# untitled.net
KiCad netlist of a schematic drawn in EAGLE
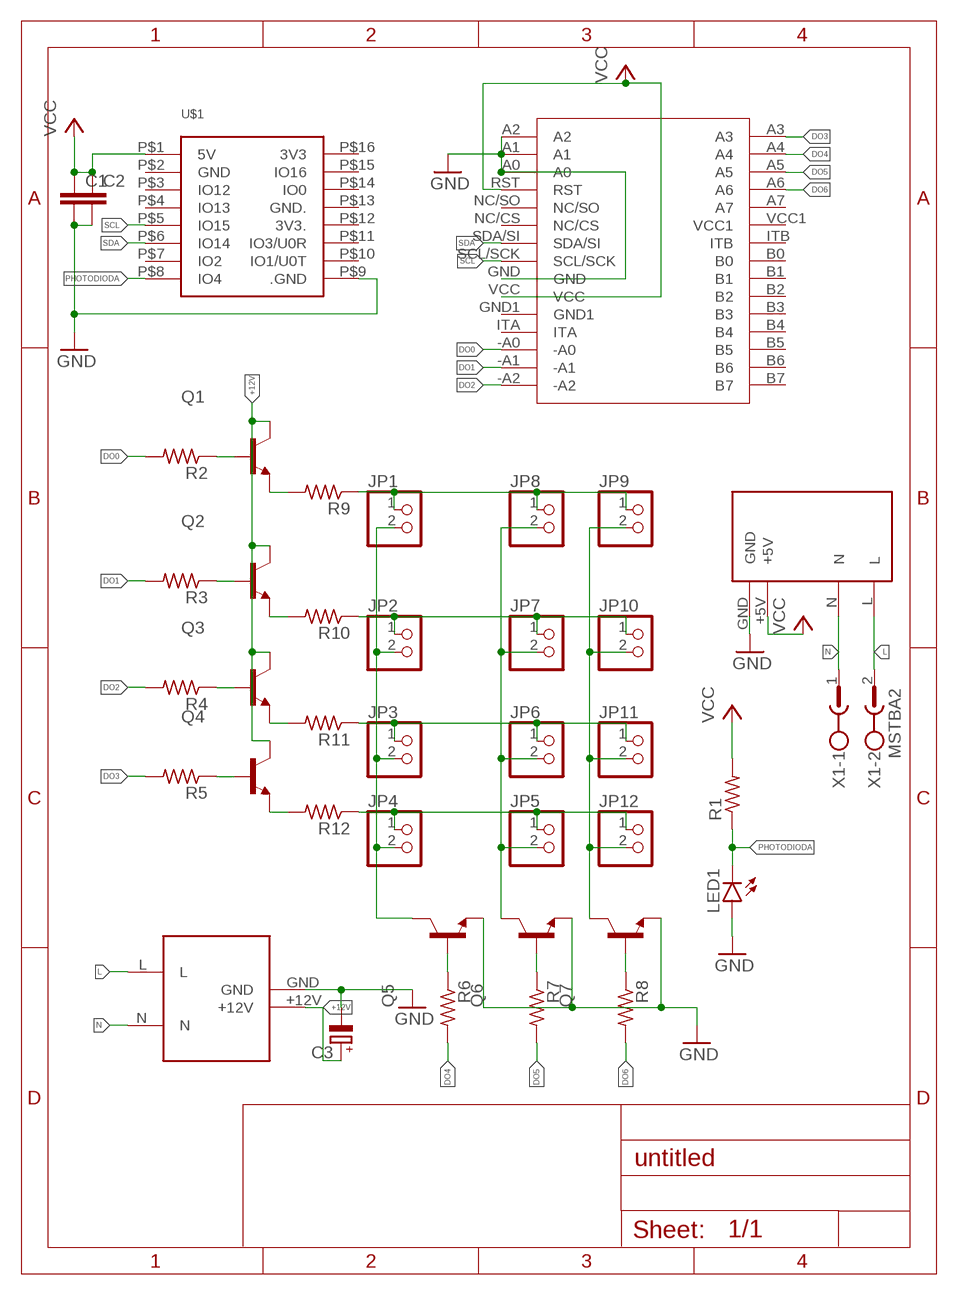
[diagram p0: schematic, sheet 1]

(export (version "E")
  (design (tool "Eeschema 10.0.6"))
  (components
    (comp (ref "C1")
      (value "C-EUC0805K")
      (footprint "eagle-import:C0805K")
      (libsource (lib "eagle-import") (part "C-EUC0805K"))
    )
    (comp (ref "C2")
      (value "C-EUC0805K")
      (footprint "eagle-import:C0805K")
      (libsource (lib "eagle-import") (part "C-EUC0805K"))
    )
    (comp (ref "C3")
      (value "CPOL-EU153CLV-0505")
      (footprint "eagle-import:153CLV-0505")
      (libsource (lib "eagle-import") (part "CPOL-EU153CLV-0505"))
    )
    (comp (ref "HLK-15M1")
      (value "HLK-15M12")
      (footprint "eagle-import:HLK-15M12")
      (libsource (lib "eagle-import") (part "HLK-15M12"))
    )
    (comp (ref "JP1")
      (value "PINHD-1X2")
      (footprint "eagle-import:1X02")
      (libsource (lib "eagle-import") (part "PINHD-1X2"))
    )
    (comp (ref "JP2")
      (value "PINHD-1X2")
      (footprint "eagle-import:1X02")
      (libsource (lib "eagle-import") (part "PINHD-1X2"))
    )
    (comp (ref "JP3")
      (value "PINHD-1X2")
      (footprint "eagle-import:1X02")
      (libsource (lib "eagle-import") (part "PINHD-1X2"))
    )
    (comp (ref "JP4")
      (value "PINHD-1X2")
      (footprint "eagle-import:1X02")
      (libsource (lib "eagle-import") (part "PINHD-1X2"))
    )
    (comp (ref "JP5")
      (value "PINHD-1X2")
      (footprint "eagle-import:1X02")
      (libsource (lib "eagle-import") (part "PINHD-1X2"))
    )
    (comp (ref "JP6")
      (value "PINHD-1X2")
      (footprint "eagle-import:1X02")
      (libsource (lib "eagle-import") (part "PINHD-1X2"))
    )
    (comp (ref "JP7")
      (value "PINHD-1X2")
      (footprint "eagle-import:1X02")
      (libsource (lib "eagle-import") (part "PINHD-1X2"))
    )
    (comp (ref "JP8")
      (value "PINHD-1X2")
      (footprint "eagle-import:1X02")
      (libsource (lib "eagle-import") (part "PINHD-1X2"))
    )
    (comp (ref "JP9")
      (value "PINHD-1X2")
      (footprint "eagle-import:1X02")
      (libsource (lib "eagle-import") (part "PINHD-1X2"))
    )
    (comp (ref "JP10")
      (value "PINHD-1X2")
      (footprint "eagle-import:1X02")
      (libsource (lib "eagle-import") (part "PINHD-1X2"))
    )
    (comp (ref "JP11")
      (value "PINHD-1X2")
      (footprint "eagle-import:1X02")
      (libsource (lib "eagle-import") (part "PINHD-1X2"))
    )
    (comp (ref "JP12")
      (value "PINHD-1X2")
      (footprint "eagle-import:1X02")
      (libsource (lib "eagle-import") (part "PINHD-1X2"))
    )
    (comp (ref "LED1")
      (value "LED5MM")
      (footprint "eagle-import:LED5MM")
      (libsource (lib "eagle-import") (part "LED5MM"))
    )
    (comp (ref "MCP1")
      (value "MCP23017")
      (footprint "eagle-import:MCP23017")
      (libsource (lib "eagle-import") (part "MCP23017"))
    )
    (comp (ref "Q1")
      (value "BCW31SMD")
      (footprint "eagle-import:SOT23-BEC")
      (fields (field (name "MF") "ON Semiconductor") (field (name "MP") "BCW31"))
      (libsource (lib "eagle-import") (part "BCW31SMD"))
    )
    (comp (ref "Q2")
      (value "BCW31SMD")
      (footprint "eagle-import:SOT23-BEC")
      (fields (field (name "MF") "ON Semiconductor") (field (name "MP") "BCW31"))
      (libsource (lib "eagle-import") (part "BCW31SMD"))
    )
    (comp (ref "Q3")
      (value "BCW31SMD")
      (footprint "eagle-import:SOT23-BEC")
      (fields (field (name "MF") "ON Semiconductor") (field (name "MP") "BCW31"))
      (libsource (lib "eagle-import") (part "BCW31SMD"))
    )
    (comp (ref "Q4")
      (value "BCW31SMD")
      (footprint "eagle-import:SOT23-BEC")
      (fields (field (name "MF") "ON Semiconductor") (field (name "MP") "BCW31"))
      (libsource (lib "eagle-import") (part "BCW31SMD"))
    )
    (comp (ref "Q5")
      (value "BCW31SMD")
      (footprint "eagle-import:SOT23-BEC")
      (fields (field (name "MF") "ON Semiconductor") (field (name "MP") "BCW31"))
      (libsource (lib "eagle-import") (part "BCW31SMD"))
    )
    (comp (ref "Q6")
      (value "BCW31SMD")
      (footprint "eagle-import:SOT23-BEC")
      (fields (field (name "MF") "ON Semiconductor") (field (name "MP") "BCW31"))
      (libsource (lib "eagle-import") (part "BCW31SMD"))
    )
    (comp (ref "Q7")
      (value "BCW31SMD")
      (footprint "eagle-import:SOT23-BEC")
      (fields (field (name "MF") "ON Semiconductor") (field (name "MP") "BCW31"))
      (libsource (lib "eagle-import") (part "BCW31SMD"))
    )
    (comp (ref "R1")
      (value "R-US_M0805")
      (footprint "eagle-import:M0805")
      (libsource (lib "eagle-import") (part "R-US_M0805"))
    )
    (comp (ref "R2")
      (value "R-US_M0805")
      (footprint "eagle-import:M0805")
      (libsource (lib "eagle-import") (part "R-US_M0805"))
    )
    (comp (ref "R3")
      (value "R-US_M0805")
      (footprint "eagle-import:M0805")
      (libsource (lib "eagle-import") (part "R-US_M0805"))
    )
    (comp (ref "R4")
      (value "R-US_M0805")
      (footprint "eagle-import:M0805")
      (libsource (lib "eagle-import") (part "R-US_M0805"))
    )
    (comp (ref "R5")
      (value "R-US_M0805")
      (footprint "eagle-import:M0805")
      (libsource (lib "eagle-import") (part "R-US_M0805"))
    )
    (comp (ref "R6")
      (value "R-US_M0805")
      (footprint "eagle-import:M0805")
      (libsource (lib "eagle-import") (part "R-US_M0805"))
    )
    (comp (ref "R7")
      (value "R-US_M0805")
      (footprint "eagle-import:M0805")
      (libsource (lib "eagle-import") (part "R-US_M0805"))
    )
    (comp (ref "R8")
      (value "R-US_M0805")
      (footprint "eagle-import:M0805")
      (libsource (lib "eagle-import") (part "R-US_M0805"))
    )
    (comp (ref "R9")
      (value "R-US_M0805")
      (footprint "eagle-import:M0805")
      (libsource (lib "eagle-import") (part "R-US_M0805"))
    )
    (comp (ref "R10")
      (value "R-US_M0805")
      (footprint "eagle-import:M0805")
      (libsource (lib "eagle-import") (part "R-US_M0805"))
    )
    (comp (ref "R11")
      (value "R-US_M0805")
      (footprint "eagle-import:M0805")
      (libsource (lib "eagle-import") (part "R-US_M0805"))
    )
    (comp (ref "R12")
      (value "R-US_M0805")
      (footprint "eagle-import:M0805")
      (libsource (lib "eagle-import") (part "R-US_M0805"))
    )
    (comp (ref "U$1")
      (value "ESP32-CAM")
      (footprint "eagle-import:ESP32-CAM")
      (fields (field (name "MF") "AI-Thinker"))
      (libsource (lib "eagle-import") (part "ESP32-CAM"))
    )
    (comp (ref "WX-DC1")
      (value "WX-DC12003")
      (footprint "eagle-import:WX-DC12003")
      (libsource (lib "eagle-import") (part "WX-DC12003"))
    )
    (comp (ref "X1")
      (value "MSTBA2")
      (footprint "eagle-import:MSTBA2")
      (fields (field (name "MF") "FARNELL") (field (name "MPN") "1757242"))
      (libsource (lib "eagle-import") (part "MSTBA2"))
    )
  )
  (nets
    (net (code "1") (name "+12V") (class "Default")
      (node (ref "C3") (pin "+") (pinfunction "+_+") (pintype "passive"))
      (node (ref "HLK-15M1") (pin "+12V") (pinfunction "+12V_+12V") (pintype "bidirectional"))
      (node (ref "Q1") (pin "C") (pinfunction "C_C") (pintype "passive"))
      (node (ref "Q2") (pin "C") (pinfunction "C_C") (pintype "passive"))
      (node (ref "Q3") (pin "C") (pinfunction "C_C") (pintype "passive"))
      (node (ref "Q4") (pin "C") (pinfunction "C_C") (pintype "passive"))
    )
    (net (code "2") (name "DO0") (class "Default")
      (node (ref "MCP1") (pin "-A0") (pinfunction "-A0_-A0") (pintype "bidirectional"))
      (node (ref "R2") (pin "2") (pinfunction "2_2") (pintype "passive"))
    )
    (net (code "3") (name "DO1") (class "Default")
      (node (ref "MCP1") (pin "-A1") (pinfunction "-A1_-A1") (pintype "bidirectional"))
      (node (ref "R3") (pin "2") (pinfunction "2_2") (pintype "passive"))
    )
    (net (code "4") (name "DO2") (class "Default")
      (node (ref "MCP1") (pin "-A2") (pinfunction "-A2_-A2") (pintype "bidirectional"))
      (node (ref "R4") (pin "2") (pinfunction "2_2") (pintype "passive"))
    )
    (net (code "5") (name "DO3") (class "Default")
      (node (ref "MCP1") (pin "A3") (pinfunction "A3_A3") (pintype "bidirectional"))
      (node (ref "R5") (pin "2") (pinfunction "2_2") (pintype "passive"))
    )
    (net (code "6") (name "DO4") (class "Default")
      (node (ref "MCP1") (pin "A4") (pinfunction "A4_A4") (pintype "bidirectional"))
      (node (ref "R6") (pin "2") (pinfunction "2_2") (pintype "passive"))
    )
    (net (code "7") (name "DO5") (class "Default")
      (node (ref "MCP1") (pin "A5") (pinfunction "A5_A5") (pintype "bidirectional"))
      (node (ref "R7") (pin "2") (pinfunction "2_2") (pintype "passive"))
    )
    (net (code "8") (name "DO6") (class "Default")
      (node (ref "MCP1") (pin "A6") (pinfunction "A6_A6") (pintype "bidirectional"))
      (node (ref "R8") (pin "2") (pinfunction "2_2") (pintype "passive"))
    )
    (net (code "9") (name "GND") (class "Default")
      (node (ref "C1") (pin "2") (pinfunction "2_2") (pintype "passive"))
      (node (ref "C2") (pin "2") (pinfunction "2_2") (pintype "passive"))
      (node (ref "C3") (pin "-") (pinfunction "-_-") (pintype "passive"))
      (node (ref "HLK-15M1") (pin "GND") (pinfunction "GND_GND") (pintype "bidirectional"))
      (node (ref "LED1") (pin "A") (pinfunction "A_A") (pintype "passive"))
      (node (ref "MCP1") (pin "A0") (pinfunction "A0_A0") (pintype "bidirectional"))
      (node (ref "MCP1") (pin "A1") (pinfunction "A1_A1") (pintype "bidirectional"))
      (node (ref "MCP1") (pin "A2") (pinfunction "A2_A2") (pintype "bidirectional"))
      (node (ref "MCP1") (pin "GND") (pinfunction "GND_GND") (pintype "bidirectional"))
      (node (ref "Q5") (pin "E") (pinfunction "E_E") (pintype "passive"))
      (node (ref "Q6") (pin "E") (pinfunction "E_E") (pintype "passive"))
      (node (ref "Q7") (pin "E") (pinfunction "E_E") (pintype "passive"))
      (node (ref "U$1") (pin "P$9") (pinfunction ".GND_P$9") (pintype "bidirectional"))
      (node (ref "WX-DC1") (pin "GND") (pinfunction "GND_GND") (pintype "bidirectional"))
    )
    (net (code "10") (name "L") (class "Default")
      (node (ref "HLK-15M1") (pin "L") (pinfunction "L_L") (pintype "bidirectional"))
      (node (ref "WX-DC1") (pin "L") (pinfunction "L_L") (pintype "bidirectional"))
      (node (ref "X1") (pin "2") (pinfunction "1_2") (pintype "passive"))
    )
    (net (code "11") (name "N") (class "Default")
      (node (ref "HLK-15M1") (pin "N") (pinfunction "N_N") (pintype "bidirectional"))
      (node (ref "WX-DC1") (pin "N") (pinfunction "N_N") (pintype "bidirectional"))
      (node (ref "X1") (pin "1") (pinfunction "1_1") (pintype "passive"))
    )
    (net (code "12") (name "Net-(JP1-Pad1)") (class "Default")
      (node (ref "JP1") (pin "1") (pinfunction "1_1") (pintype "passive"))
      (node (ref "JP8") (pin "1") (pinfunction "1_1") (pintype "passive"))
      (node (ref "JP9") (pin "1") (pinfunction "1_1") (pintype "passive"))
      (node (ref "R9") (pin "1") (pinfunction "1_1") (pintype "passive"))
    )
    (net (code "13") (name "Net-(JP1-Pad2)") (class "Default")
      (node (ref "JP1") (pin "2") (pinfunction "2_2") (pintype "passive"))
      (node (ref "JP2") (pin "2") (pinfunction "2_2") (pintype "passive"))
      (node (ref "JP3") (pin "2") (pinfunction "2_2") (pintype "passive"))
      (node (ref "JP4") (pin "2") (pinfunction "2_2") (pintype "passive"))
      (node (ref "Q5") (pin "C") (pinfunction "C_C") (pintype "passive"))
    )
    (net (code "14") (name "Net-(JP5-Pad2)") (class "Default")
      (node (ref "JP5") (pin "2") (pinfunction "2_2") (pintype "passive"))
      (node (ref "JP6") (pin "2") (pinfunction "2_2") (pintype "passive"))
      (node (ref "JP7") (pin "2") (pinfunction "2_2") (pintype "passive"))
      (node (ref "JP8") (pin "2") (pinfunction "2_2") (pintype "passive"))
      (node (ref "Q6") (pin "C") (pinfunction "C_C") (pintype "passive"))
    )
    (net (code "15") (name "Net-(JP10-Pad1)") (class "Default")
      (node (ref "JP10") (pin "1") (pinfunction "1_1") (pintype "passive"))
      (node (ref "JP2") (pin "1") (pinfunction "1_1") (pintype "passive"))
      (node (ref "JP7") (pin "1") (pinfunction "1_1") (pintype "passive"))
      (node (ref "R10") (pin "1") (pinfunction "1_1") (pintype "passive"))
    )
    (net (code "16") (name "Net-(JP10-Pad2)") (class "Default")
      (node (ref "JP10") (pin "2") (pinfunction "2_2") (pintype "passive"))
      (node (ref "JP11") (pin "2") (pinfunction "2_2") (pintype "passive"))
      (node (ref "JP12") (pin "2") (pinfunction "2_2") (pintype "passive"))
      (node (ref "JP9") (pin "2") (pinfunction "2_2") (pintype "passive"))
      (node (ref "Q7") (pin "C") (pinfunction "C_C") (pintype "passive"))
    )
    (net (code "17") (name "Net-(JP11-Pad1)") (class "Default")
      (node (ref "JP11") (pin "1") (pinfunction "1_1") (pintype "passive"))
      (node (ref "JP3") (pin "1") (pinfunction "1_1") (pintype "passive"))
      (node (ref "JP6") (pin "1") (pinfunction "1_1") (pintype "passive"))
      (node (ref "R11") (pin "1") (pinfunction "1_1") (pintype "passive"))
    )
    (net (code "18") (name "Net-(JP12-Pad1)") (class "Default")
      (node (ref "JP12") (pin "1") (pinfunction "1_1") (pintype "passive"))
      (node (ref "JP4") (pin "1") (pinfunction "1_1") (pintype "passive"))
      (node (ref "JP5") (pin "1") (pinfunction "1_1") (pintype "passive"))
      (node (ref "R12") (pin "1") (pinfunction "1_1") (pintype "passive"))
    )
    (net (code "19") (name "Net-(Q1-PadB)") (class "Default")
      (node (ref "Q1") (pin "B") (pinfunction "B_B") (pintype "passive"))
      (node (ref "R2") (pin "1") (pinfunction "1_1") (pintype "passive"))
    )
    (net (code "20") (name "Net-(Q1-PadE)") (class "Default")
      (node (ref "Q1") (pin "E") (pinfunction "E_E") (pintype "passive"))
      (node (ref "R9") (pin "2") (pinfunction "2_2") (pintype "passive"))
    )
    (net (code "21") (name "Net-(Q2-PadB)") (class "Default")
      (node (ref "Q2") (pin "B") (pinfunction "B_B") (pintype "passive"))
      (node (ref "R3") (pin "1") (pinfunction "1_1") (pintype "passive"))
    )
    (net (code "22") (name "Net-(Q2-PadE)") (class "Default")
      (node (ref "Q2") (pin "E") (pinfunction "E_E") (pintype "passive"))
      (node (ref "R10") (pin "2") (pinfunction "2_2") (pintype "passive"))
    )
    (net (code "23") (name "Net-(Q3-PadB)") (class "Default")
      (node (ref "Q3") (pin "B") (pinfunction "B_B") (pintype "passive"))
      (node (ref "R4") (pin "1") (pinfunction "1_1") (pintype "passive"))
    )
    (net (code "24") (name "Net-(Q3-PadE)") (class "Default")
      (node (ref "Q3") (pin "E") (pinfunction "E_E") (pintype "passive"))
      (node (ref "R11") (pin "2") (pinfunction "2_2") (pintype "passive"))
    )
    (net (code "25") (name "Net-(Q4-PadB)") (class "Default")
      (node (ref "Q4") (pin "B") (pinfunction "B_B") (pintype "passive"))
      (node (ref "R5") (pin "1") (pinfunction "1_1") (pintype "passive"))
    )
    (net (code "26") (name "Net-(Q4-PadE)") (class "Default")
      (node (ref "Q4") (pin "E") (pinfunction "E_E") (pintype "passive"))
      (node (ref "R12") (pin "2") (pinfunction "2_2") (pintype "passive"))
    )
    (net (code "27") (name "Net-(Q5-PadB)") (class "Default")
      (node (ref "Q5") (pin "B") (pinfunction "B_B") (pintype "passive"))
      (node (ref "R6") (pin "1") (pinfunction "1_1") (pintype "passive"))
    )
    (net (code "28") (name "Net-(Q6-PadB)") (class "Default")
      (node (ref "Q6") (pin "B") (pinfunction "B_B") (pintype "passive"))
      (node (ref "R7") (pin "1") (pinfunction "1_1") (pintype "passive"))
    )
    (net (code "29") (name "Net-(Q7-PadB)") (class "Default")
      (node (ref "Q7") (pin "B") (pinfunction "B_B") (pintype "passive"))
      (node (ref "R8") (pin "1") (pinfunction "1_1") (pintype "passive"))
    )
    (net (code "30") (name "PHOTODIODA") (class "Default")
      (node (ref "LED1") (pin "K") (pinfunction "C_K") (pintype "passive"))
      (node (ref "R1") (pin "1") (pinfunction "1_1") (pintype "passive"))
      (node (ref "U$1") (pin "P$8") (pinfunction "IO4_P$8") (pintype "bidirectional"))
    )
    (net (code "31") (name "SCL") (class "Default")
      (node (ref "MCP1") (pin "SCL/SCK") (pinfunction "SCL/SCK_SCL/SCK") (pintype "bidirectional"))
      (node (ref "U$1") (pin "P$5") (pinfunction "IO15_P$5") (pintype "bidirectional"))
    )
    (net (code "32") (name "SDA") (class "Default")
      (node (ref "MCP1") (pin "SDA/SI") (pinfunction "SDA/SI_SDA/SI") (pintype "bidirectional"))
      (node (ref "U$1") (pin "P$6") (pinfunction "IO14_P$6") (pintype "bidirectional"))
    )
    (net (code "33") (name "VCC") (class "Default")
      (node (ref "C1") (pin "1") (pinfunction "1_1") (pintype "passive"))
      (node (ref "C2") (pin "1") (pinfunction "1_1") (pintype "passive"))
      (node (ref "MCP1") (pin "RST") (pinfunction "RST_RST") (pintype "bidirectional"))
      (node (ref "MCP1") (pin "VCC") (pinfunction "VCC_VCC") (pintype "bidirectional"))
      (node (ref "R1") (pin "2") (pinfunction "2_2") (pintype "passive"))
      (node (ref "U$1") (pin "P$1") (pinfunction "5V_P$1") (pintype "bidirectional"))
      (node (ref "WX-DC1") (pin "+5V") (pinfunction "+5V_+5V") (pintype "bidirectional"))
    )
    (net (code "34") (name "unconnected-(MCP1-PadA7)") (class "Default")
      (node (ref "MCP1") (pin "A7") (pinfunction "A7_A7") (pintype "bidirectional"))
    )
    (net (code "35") (name "unconnected-(MCP1-PadB0)") (class "Default")
      (node (ref "MCP1") (pin "B0") (pinfunction "B0_B0") (pintype "bidirectional"))
    )
    (net (code "36") (name "unconnected-(MCP1-PadB1)") (class "Default")
      (node (ref "MCP1") (pin "B1") (pinfunction "B1_B1") (pintype "bidirectional"))
    )
    (net (code "37") (name "unconnected-(MCP1-PadB2)") (class "Default")
      (node (ref "MCP1") (pin "B2") (pinfunction "B2_B2") (pintype "bidirectional"))
    )
    (net (code "38") (name "unconnected-(MCP1-PadB3)") (class "Default")
      (node (ref "MCP1") (pin "B3") (pinfunction "B3_B3") (pintype "bidirectional"))
    )
    (net (code "39") (name "unconnected-(MCP1-PadB4)") (class "Default")
      (node (ref "MCP1") (pin "B4") (pinfunction "B4_B4") (pintype "bidirectional"))
    )
    (net (code "40") (name "unconnected-(MCP1-PadB5)") (class "Default")
      (node (ref "MCP1") (pin "B5") (pinfunction "B5_B5") (pintype "bidirectional"))
    )
    (net (code "41") (name "unconnected-(MCP1-PadB6)") (class "Default")
      (node (ref "MCP1") (pin "B6") (pinfunction "B6_B6") (pintype "bidirectional"))
    )
    (net (code "42") (name "unconnected-(MCP1-PadB7)") (class "Default")
      (node (ref "MCP1") (pin "B7") (pinfunction "B7_B7") (pintype "bidirectional"))
    )
    (net (code "43") (name "unconnected-(MCP1-PadGND1)") (class "Default")
      (node (ref "MCP1") (pin "GND1") (pinfunction "GND1_GND1") (pintype "bidirectional"))
    )
    (net (code "44") (name "unconnected-(MCP1-PadITA)") (class "Default")
      (node (ref "MCP1") (pin "ITA") (pinfunction "ITA_ITA") (pintype "bidirectional"))
    )
    (net (code "45") (name "unconnected-(MCP1-PadITB)") (class "Default")
      (node (ref "MCP1") (pin "ITB") (pinfunction "ITB_ITB") (pintype "bidirectional"))
    )
    (net (code "46") (name "unconnected-(MCP1-PadNC{slash}CS)") (class "Default")
      (node (ref "MCP1") (pin "NC/CS") (pinfunction "NC/CS_NC/CS") (pintype "bidirectional"))
    )
    (net (code "47") (name "unconnected-(MCP1-PadNC{slash}SO)") (class "Default")
      (node (ref "MCP1") (pin "NC/SO") (pinfunction "NC/SO_NC/SO") (pintype "bidirectional"))
    )
    (net (code "48") (name "unconnected-(MCP1-PadVCC1)") (class "Default")
      (node (ref "MCP1") (pin "VCC1") (pinfunction "VCC1_VCC1") (pintype "bidirectional"))
    )
    (net (code "49") (name "unconnected-(U$1-3V3-PadP$16)") (class "Default")
      (node (ref "U$1") (pin "P$16") (pinfunction "3V3_P$16") (pintype "bidirectional"))
    )
    (net (code "50") (name "unconnected-(U$1-3V3.-PadP$12)") (class "Default")
      (node (ref "U$1") (pin "P$12") (pinfunction "3V3._P$12") (pintype "bidirectional"))
    )
    (net (code "51") (name "unconnected-(U$1-GND-PadP$2)") (class "Default")
      (node (ref "U$1") (pin "P$2") (pinfunction "GND_P$2") (pintype "bidirectional"))
    )
    (net (code "52") (name "unconnected-(U$1-GND.-PadP$13)") (class "Default")
      (node (ref "U$1") (pin "P$13") (pinfunction "GND._P$13") (pintype "bidirectional"))
    )
    (net (code "53") (name "unconnected-(U$1-IO0-PadP$14)") (class "Default")
      (node (ref "U$1") (pin "P$14") (pinfunction "IO0_P$14") (pintype "bidirectional"))
    )
    (net (code "54") (name "unconnected-(U$1-IO1{slash}U0T-PadP$10)") (class "Default")
      (node (ref "U$1") (pin "P$10") (pinfunction "IO1/U0T_P$10") (pintype "bidirectional"))
    )
    (net (code "55") (name "unconnected-(U$1-IO2-PadP$7)") (class "Default")
      (node (ref "U$1") (pin "P$7") (pinfunction "IO2_P$7") (pintype "bidirectional"))
    )
    (net (code "56") (name "unconnected-(U$1-IO3{slash}U0R-PadP$11)") (class "Default")
      (node (ref "U$1") (pin "P$11") (pinfunction "IO3/U0R_P$11") (pintype "bidirectional"))
    )
    (net (code "57") (name "unconnected-(U$1-IO12-PadP$3)") (class "Default")
      (node (ref "U$1") (pin "P$3") (pinfunction "IO12_P$3") (pintype "bidirectional"))
    )
    (net (code "58") (name "unconnected-(U$1-IO13-PadP$4)") (class "Default")
      (node (ref "U$1") (pin "P$4") (pinfunction "IO13_P$4") (pintype "bidirectional"))
    )
    (net (code "59") (name "unconnected-(U$1-IO16-PadP$15)") (class "Default")
      (node (ref "U$1") (pin "P$15") (pinfunction "IO16_P$15") (pintype "bidirectional"))
    )
  )
)
